# batterietest.net
KiCad netlist of a schematic drawn in EAGLE
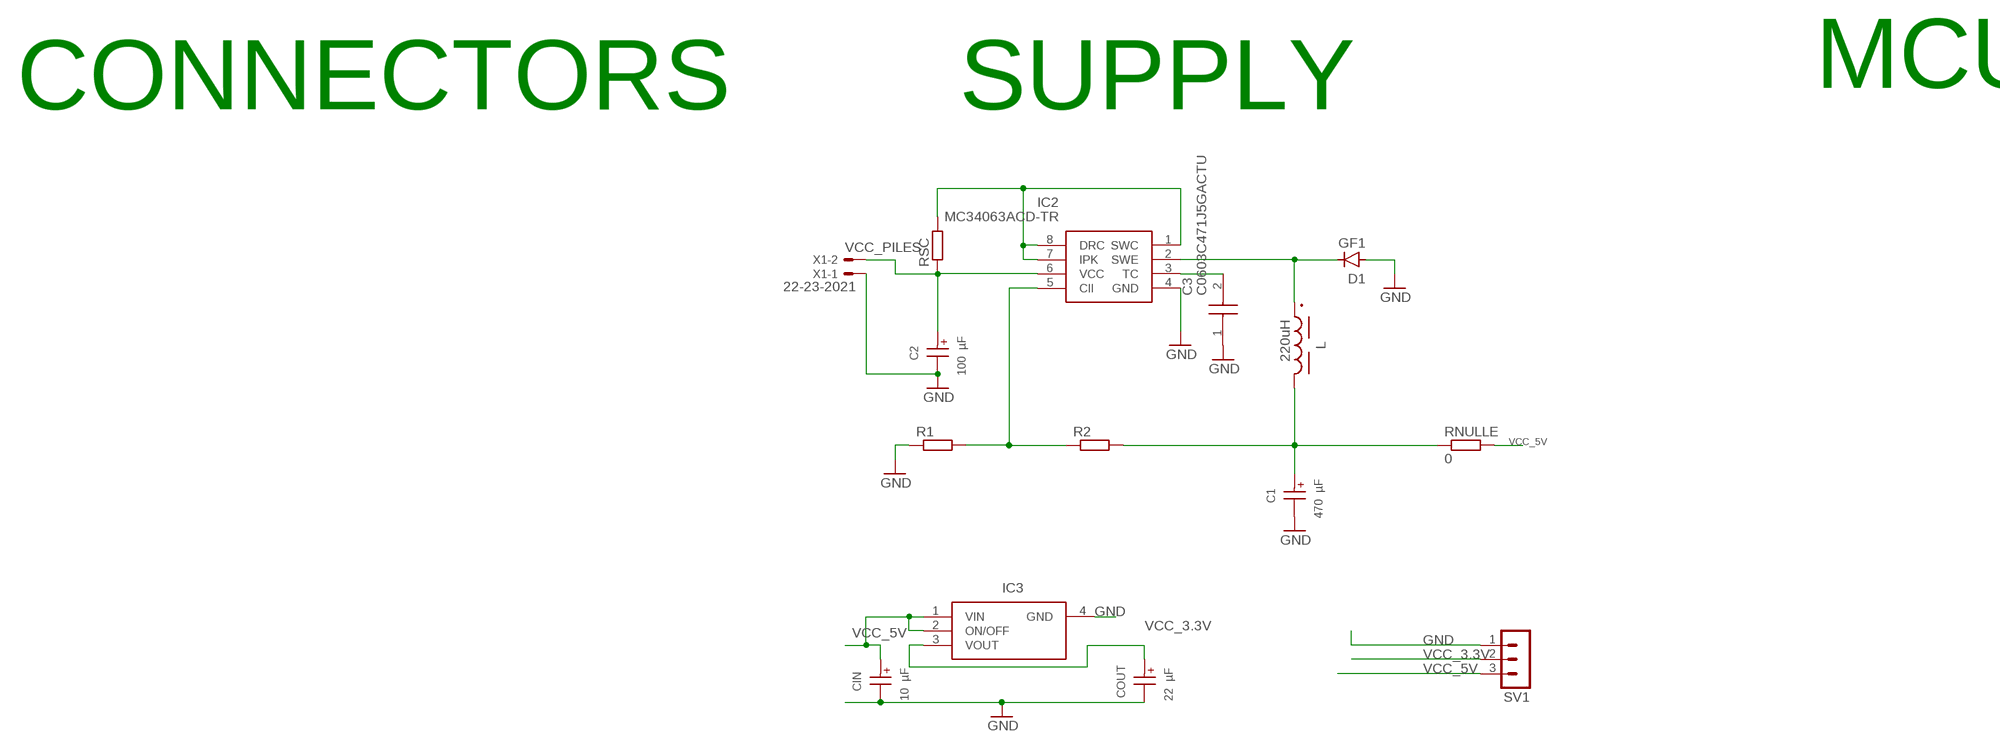
[diagram p0: schematic, sheet 1]

(export (version "E")
  (design (tool "Eeschema 10.0.6"))
  (components
    (comp (ref "C1")
      (value "470 µF")
      (footprint "eagle-import:WCAP-ASLL_8X10.5(DXL)")
      (libsource (lib "eagle-import") (part "WCAP-ASLL_8X10.5_865060353009"))
    )
    (comp (ref "C2")
      (value "100 µF")
      (footprint "eagle-import:WCAP-ASLL_6.3X7.7(DXL)")
      (libsource (lib "eagle-import") (part "WCAP-ASLL_6.3X7.7_865060445005"))
    )
    (comp (ref "C3")
      (value "C0603C471J5GACTU")
      (footprint "eagle-import:C0603")
      (fields (field (name "MOUSER_PART_NUMBER") "80-C0603C471J5G"))
      (libsource (lib "eagle-import") (part "C0603C471J5GACTU"))
    )
    (comp (ref "CIN")
      (value "10 µF")
      (footprint "eagle-import:WCAP-ASLL_4X5.5(DXL)")
      (libsource (lib "eagle-import") (part "WCAP-ASLL_4X5.5_865060440001"))
    )
    (comp (ref "COUT")
      (value "22 µF")
      (footprint "eagle-import:WCAP-ASLL_5X5.5(DXL)")
      (libsource (lib "eagle-import") (part "WCAP-ASLL_5X5.5_865060442002"))
    )
    (comp (ref "D1")
      (value "GF1")
      (footprint "eagle-import:SMA-DO214AC")
      (libsource (lib "eagle-import") (part "GF1"))
    )
    (comp (ref "IC2")
      (value "MC34063ACD-TR")
      (footprint "eagle-import:SOIC127P600X175-8N")
      (fields (field (name "MOUSER_PART_NUMBER") "511-MC34063ACD-TR"))
      (libsource (lib "eagle-import") (part "MC34063ACD-TR"))
    )
    (comp (ref "IC3")
      (value "NCV33375ST3.3T3G")
      (footprint "eagle-import:SOT230P700X175-4N")
      (fields (field (name "MOUSER_PART_NUMBER") "863-NCV33375ST3.3T3G"))
      (libsource (lib "eagle-import") (part "NCV33375ST3.3T3G"))
    )
    (comp (ref "L")
      (value "220uH")
      (footprint "eagle-import:WE-PDA_1260")
      (libsource (lib "eagle-import") (part "WE-PDA_1260_784771221"))
    )
    (comp (ref "R1")
      (value "R-EU_R0603")
      (footprint "eagle-import:R0603")
      (libsource (lib "eagle-import") (part "R-EU_R0603"))
    )
    (comp (ref "R2")
      (value "R-EU_R0603")
      (footprint "eagle-import:R0603")
      (libsource (lib "eagle-import") (part "R-EU_R0603"))
    )
    (comp (ref "RNULLE")
      (value "0")
      (footprint "eagle-import:R0603")
      (libsource (lib "eagle-import") (part "R-EU_R0603"))
    )
    (comp (ref "RSC")
      (value "R-EU_R1206W")
      (footprint "eagle-import:R1206W")
      (libsource (lib "eagle-import") (part "R-EU_R1206W"))
    )
    (comp (ref "SV1")
      (value "MA03-1")
      (footprint "eagle-import:MA03-1")
      (libsource (lib "eagle-import") (part "MA03-1"))
    )
    (comp (ref "X1")
      (value "22-23-2021")
      (footprint "eagle-import:22-23-2021")
      (fields (field (name "MF") "MOLEX"))
      (libsource (lib "eagle-import") (part "22-23-2021"))
    )
  )
  (nets
    (net (code "1") (name "/VCC_3.3V") (class "Default")
      (node (ref "COUT") (pin "1") (pinfunction "+_1") (pintype "passive"))
      (node (ref "IC3") (pin "3") (pinfunction "VOUT_3") (pintype "bidirectional"))
      (node (ref "SV1") (pin "2") (pinfunction "2_2") (pintype "passive"))
    )
    (net (code "2") (name "/VCC_5V") (class "Default")
      (node (ref "CIN") (pin "1") (pinfunction "+_1") (pintype "passive"))
      (node (ref "IC3") (pin "1") (pinfunction "VIN_1") (pintype "bidirectional"))
      (node (ref "IC3") (pin "2") (pinfunction "ON/OFF_2") (pintype "bidirectional"))
      (node (ref "RNULLE") (pin "2") (pinfunction "2_2") (pintype "passive"))
      (node (ref "SV1") (pin "3") (pinfunction "3_3") (pintype "passive"))
    )
    (net (code "3") (name "/VCC_PILES") (class "Default")
      (node (ref "C2") (pin "1") (pinfunction "+_1") (pintype "passive"))
      (node (ref "IC2") (pin "6") (pinfunction "VCC_6") (pintype "bidirectional"))
      (node (ref "RSC") (pin "1") (pinfunction "1_1") (pintype "passive"))
      (node (ref "X1") (pin "2") (pinfunction "S_2") (pintype "passive"))
    )
    (net (code "4") (name "GND") (class "Default")
      (node (ref "C1") (pin "2") (pinfunction "-_2") (pintype "passive"))
      (node (ref "C2") (pin "2") (pinfunction "-_2") (pintype "passive"))
      (node (ref "C3") (pin "1") (pinfunction "1_1") (pintype "bidirectional"))
      (node (ref "CIN") (pin "2") (pinfunction "-_2") (pintype "passive"))
      (node (ref "COUT") (pin "2") (pinfunction "-_2") (pintype "passive"))
      (node (ref "D1") (pin "A") (pinfunction "A_A") (pintype "passive"))
      (node (ref "IC2") (pin "4") (pinfunction "GND_4") (pintype "bidirectional"))
      (node (ref "IC3") (pin "4") (pinfunction "GND_4") (pintype "bidirectional"))
      (node (ref "R1") (pin "1") (pinfunction "1_1") (pintype "passive"))
      (node (ref "SV1") (pin "1") (pinfunction "1_1") (pintype "passive"))
      (node (ref "X1") (pin "1") (pinfunction "S_1") (pintype "passive"))
    )
    (net (code "5") (name "Net-(C1-+)") (class "Default")
      (node (ref "C1") (pin "1") (pinfunction "+_1") (pintype "passive"))
      (node (ref "L") (pin "2") (pinfunction "2_2") (pintype "passive"))
      (node (ref "R2") (pin "2") (pinfunction "2_2") (pintype "passive"))
      (node (ref "RNULLE") (pin "1") (pinfunction "1_1") (pintype "passive"))
    )
    (net (code "6") (name "Net-(D1-C)") (class "Default")
      (node (ref "D1") (pin "K") (pinfunction "C_K") (pintype "passive"))
      (node (ref "IC2") (pin "2") (pinfunction "SWE_2") (pintype "bidirectional"))
      (node (ref "L") (pin "1") (pinfunction "1_1") (pintype "passive"))
    )
    (net (code "7") (name "Net-(IC2-CII)") (class "Default")
      (node (ref "IC2") (pin "5") (pinfunction "CII_5") (pintype "bidirectional"))
      (node (ref "R1") (pin "2") (pinfunction "2_2") (pintype "passive"))
      (node (ref "R2") (pin "1") (pinfunction "1_1") (pintype "passive"))
    )
    (net (code "8") (name "Net-(IC2-DRC)") (class "Default")
      (node (ref "IC2") (pin "1") (pinfunction "SWC_1") (pintype "bidirectional"))
      (node (ref "IC2") (pin "7") (pinfunction "IPK_7") (pintype "bidirectional"))
      (node (ref "IC2") (pin "8") (pinfunction "DRC_8") (pintype "bidirectional"))
      (node (ref "RSC") (pin "2") (pinfunction "2_2") (pintype "passive"))
    )
    (net (code "9") (name "Net-(IC2-TC)") (class "Default")
      (node (ref "C3") (pin "2") (pinfunction "2_2") (pintype "bidirectional"))
      (node (ref "IC2") (pin "3") (pinfunction "TC_3") (pintype "bidirectional"))
    )
  )
)
